# led-wt32-eth01.net
KiCad netlist of a schematic drawn in Altium Designer
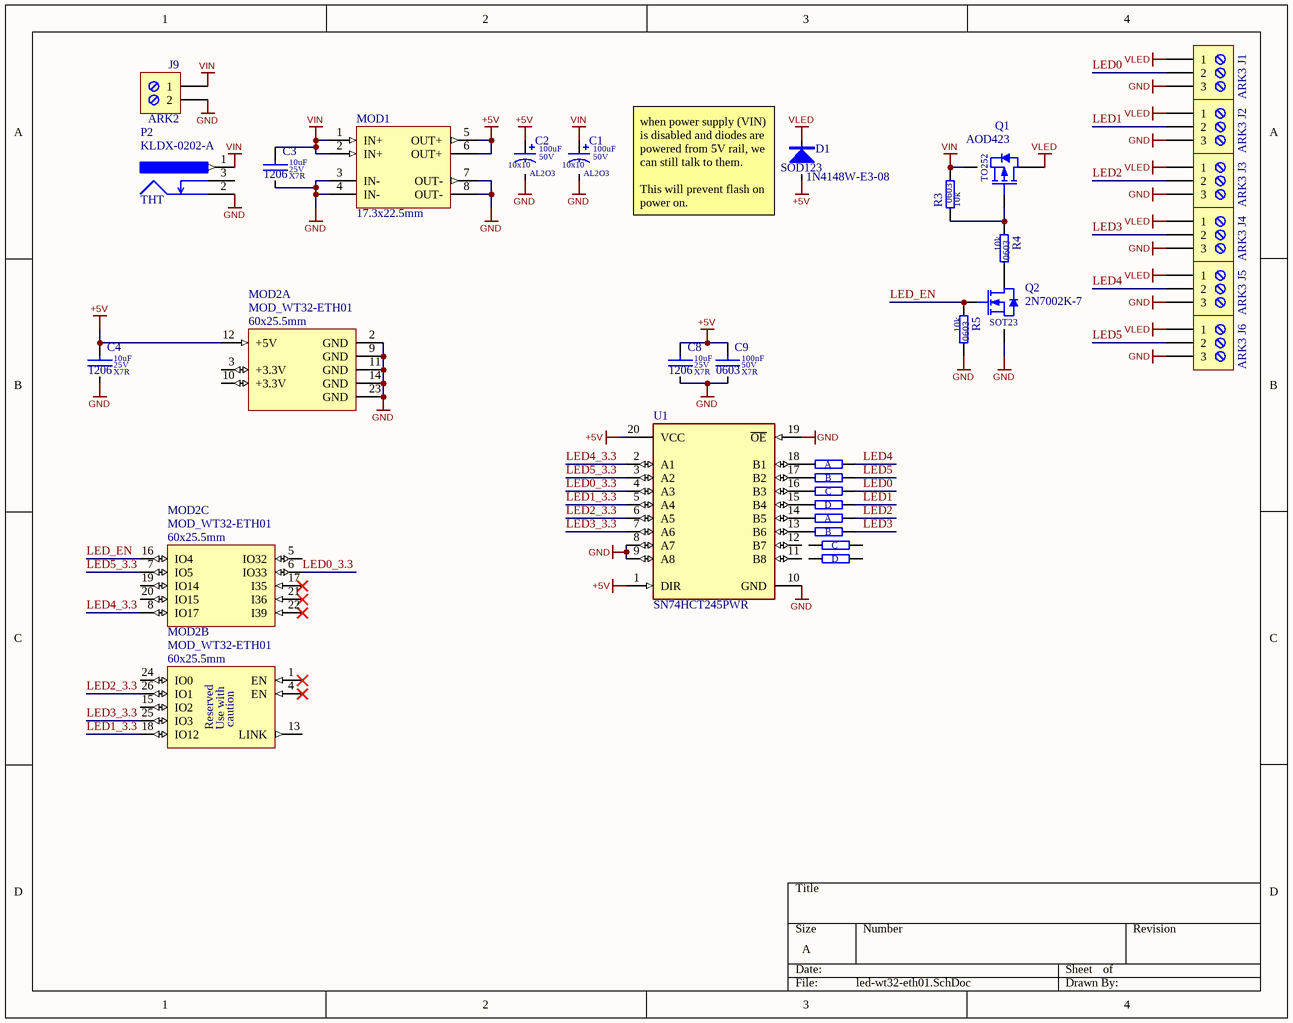
[diagram p0: led-wt32-eth01.SchDoc]

(export (version "E")
  (design (tool "Eeschema 10.0.6"))
  (components
    (comp (ref "C1")
      (value "100uF")
      (footprint "CE_D_10x10_SMD")
      (description "Polarized Capacitor")
      (fields
        (field (name "DIELECTRIC") "AL2O3")
        (field (name "SCH_FOOTPRINT") "10x10")
        (field (name "VOLTAGE") "50V")
        (field (name "PART NUMBER") "CE_100uF_50V_AL2O3_10x10_20")
        (field (name "MANUFACTURER") "Nichicon")
      )
      (libsource (lib "Library") (part "CE"))
    )
    (comp (ref "C2")
      (value "100uF")
      (footprint "CE_D_10x10_SMD")
      (description "Polarized Capacitor")
      (fields
        (field (name "DIELECTRIC") "AL2O3")
        (field (name "SCH_FOOTPRINT") "10x10")
        (field (name "VOLTAGE") "50V")
        (field (name "PART NUMBER") "CE_100uF_50V_AL2O3_10x10_20")
        (field (name "MANUFACTURER") "Nichicon")
      )
      (libsource (lib "Library") (part "CE"))
    )
    (comp (ref "C3")
      (value "10uF")
      (footprint "C_1206_3216")
      (description "Capacitor")
      (fields
        (field (name "DIELECTRIC") "X7R")
        (field (name "VOLTAGE") "25V")
        (field (name "SCH_FOOTPRINT") "1206")
        (field (name "PART NUMBER") "C_10uF_25V_X7R_1206_10")
        (field (name "MANUFACTURER") "Samsung")
      )
      (libsource (lib "Library") (part "C"))
    )
    (comp (ref "C4")
      (value "10uF")
      (footprint "C_1206_3216")
      (description "Capacitor")
      (fields
        (field (name "DIELECTRIC") "X7R")
        (field (name "VOLTAGE") "25V")
        (field (name "SCH_FOOTPRINT") "1206")
        (field (name "PART NUMBER") "C_10uF_25V_X7R_1206_10")
        (field (name "MANUFACTURER") "Samsung")
      )
      (libsource (lib "Library") (part "C"))
    )
    (comp (ref "C8")
      (value "10uF")
      (footprint "C_1206_3216")
      (description "Capacitor")
      (fields
        (field (name "DIELECTRIC") "X7R")
        (field (name "VOLTAGE") "25V")
        (field (name "SCH_FOOTPRINT") "1206")
        (field (name "PART NUMBER") "C_10uF_25V_X7R_1206_10")
        (field (name "MANUFACTURER") "Samsung")
      )
      (libsource (lib "Library") (part "C"))
    )
    (comp (ref "C9")
      (value "100nF")
      (footprint "C_0603_1608")
      (description "Capacitor")
      (fields
        (field (name "DIELECTRIC") "X7R")
        (field (name "VOLTAGE") "50V")
        (field (name "SCH_FOOTPRINT") "0603")
        (field (name "PART NUMBER") "C_100nF_50V_X7R_0603_5")
        (field (name "MANUFACTURER") "Samsung")
      )
      (libsource (lib "Library") (part "C"))
    )
    (comp (ref "D1")
      (value "1N4148W-E3-08")
      (footprint "SOD123")
      (fields
        (field (name "SCH_FOOTPRINT") "SOD123")
        (field (name "PART NUMBER") "D_1N4148W_0A15_75V_SOD123")
        (field (name "VOLTAGE") "75")
        (field (name "MANUFACTURER") "Vishay")
      )
      (libsource (lib "Library") (part "D"))
    )
    (comp (ref "J1")
      (value "ARK3")
      (footprint "J_ARK3")
      (description "ARK Screw terminal, 3-Pin")
      (fields
        (field (name "SCH_FOOTPRINT") "ARK3")
        (field (name "PART NUMBER") "J_TB-5.0-P-3P")
        (field (name "MANUFACTURER") "DEGSON ELECTRONICS")
      )
      (libsource (lib "Library") (part "J_ARK3"))
    )
    (comp (ref "J2")
      (value "ARK3")
      (footprint "J_ARK3")
      (description "ARK Screw terminal, 3-Pin")
      (fields
        (field (name "SCH_FOOTPRINT") "ARK3")
        (field (name "PART NUMBER") "J_TB-5.0-P-3P")
        (field (name "MANUFACTURER") "DEGSON ELECTRONICS")
      )
      (libsource (lib "Library") (part "J_ARK3"))
    )
    (comp (ref "J3")
      (value "ARK3")
      (footprint "J_ARK3")
      (description "ARK Screw terminal, 3-Pin")
      (fields
        (field (name "SCH_FOOTPRINT") "ARK3")
        (field (name "PART NUMBER") "J_TB-5.0-P-3P")
        (field (name "MANUFACTURER") "DEGSON ELECTRONICS")
      )
      (libsource (lib "Library") (part "J_ARK3"))
    )
    (comp (ref "J4")
      (value "ARK3")
      (footprint "J_ARK3")
      (description "ARK Screw terminal, 3-Pin")
      (fields
        (field (name "SCH_FOOTPRINT") "ARK3")
        (field (name "PART NUMBER") "J_TB-5.0-P-3P")
        (field (name "MANUFACTURER") "DEGSON ELECTRONICS")
      )
      (libsource (lib "Library") (part "J_ARK3"))
    )
    (comp (ref "J5")
      (value "ARK3")
      (footprint "J_ARK3")
      (description "ARK Screw terminal, 3-Pin")
      (fields
        (field (name "SCH_FOOTPRINT") "ARK3")
        (field (name "PART NUMBER") "J_TB-5.0-P-3P")
        (field (name "MANUFACTURER") "DEGSON ELECTRONICS")
      )
      (libsource (lib "Library") (part "J_ARK3"))
    )
    (comp (ref "J6")
      (value "ARK3")
      (footprint "J_ARK3")
      (description "ARK Screw terminal, 3-Pin")
      (fields
        (field (name "SCH_FOOTPRINT") "ARK3")
        (field (name "PART NUMBER") "J_TB-5.0-P-3P")
        (field (name "MANUFACTURER") "DEGSON ELECTRONICS")
      )
      (libsource (lib "Library") (part "J_ARK3"))
    )
    (comp (ref "J9")
      (value "ARK2")
      (footprint "J_ARK2")
      (description "ARK Screw terminal, 2-Pin")
      (fields
        (field (name "SCH_FOOTPRINT") "ARK2")
        (field (name "PART NUMBER") "J_TB-5.0-P-2P")
        (field (name "MANUFACTURER") "DEGSON ELECTRONICS")
      )
      (libsource (lib "Library") (part "J_ARK2"))
    )
    (comp (ref "MOD1")
      (value "Low cost, Aliexpress-ready DC-DC buck converter using MP1584")
      (footprint "MOD_BUCK_MP1584")
      (fields (field (name "SCH_FOOTPRINT") "17.3x22.5mm") (field (name "PART NUMBER") "MOD_BUCK_MP1584"))
      (libsource (lib "Library") (part "MOD_BUCK_MP1584"))
    )
    (comp (ref "MOD2")
      (value "MOD_WT32-ETH01")
      (footprint "MOD_WT32-ETH01")
      (fields
        (field (name "SCH_FOOTPRINT") "60x25.5mm")
        (field (name "MANUFACTURER") "WT")
        (field (name "Comment") "ESP32 with 10/100 Mbps Ethernet PHY")
      )
      (libsource (lib "Library") (part "MOD_WT32-ETH01"))
    )
    (comp (ref "P2")
      (value "KLDX-0202-A")
      (footprint "P_KLDX-0202-A")
      (description "Typical 3-pin jack power connector with switch")
      (fields
        (field (name "SCH_FOOTPRINT") "THT")
        (field (name "PART NUMBER") "P_KLDX-0202-A")
        (field (name "MANUFACTURER") "Kycon")
      )
      (libsource (lib "Library") (part "P_DC_JACK"))
    )
    (comp (ref "Q1")
      (value "AOD423")
      (footprint "DPAK_TO252-3_SC63_M")
      (fields
        (field (name "SCH_FOOTPRINT") "TO252")
        (field (name "PART NUMBER") "QP_AOD423")
        (field (name "VOLTAGE") "30V")
        (field (name "MANUFACTURER") "Alpha&Omega Semiconductor")
      )
      (libsource (lib "Library") (part "QP_GDS"))
    )
    (comp (ref "Q2")
      (value "2N7002K-7")
      (footprint "SOT23_TO236_SC59")
      (fields
        (field (name "SCH_FOOTPRINT") "SOT23")
        (field (name "PART NUMBER") "QN_2N7002K-7")
        (field (name "VOLTAGE") "60V")
        (field (name "MANUFACTURER") "Diodes Inc")
      )
      (libsource (lib "Library") (part "QN_GSD"))
    )
    (comp (ref "R3")
      (value "10k")
      (footprint "R_0603_1608")
      (fields
        (field (name "SCH_FOOTPRINT") "0603")
        (field (name "PART NUMBER") "R_10k_0603_1")
        (field (name "VOLTAGE") "75V")
        (field (name "POWER") "100mW")
      )
      (libsource (lib "Library") (part "R"))
    )
    (comp (ref "R4")
      (value "10k")
      (footprint "R_0603_1608")
      (fields
        (field (name "SCH_FOOTPRINT") "0603")
        (field (name "PART NUMBER") "R_10k_0603_1")
        (field (name "VOLTAGE") "75V")
        (field (name "POWER") "100mW")
      )
      (libsource (lib "Library") (part "R"))
    )
    (comp (ref "R5")
      (value "10k")
      (footprint "R_0603_1608")
      (fields
        (field (name "SCH_FOOTPRINT") "0603")
        (field (name "PART NUMBER") "R_10k_0603_1")
        (field (name "VOLTAGE") "75V")
        (field (name "POWER") "100mW")
      )
      (libsource (lib "Library") (part "R"))
    )
    (comp (ref "RN1")
      (value "Resistors Network")
      (footprint "RN4_0804_2010")
      (fields
        (field (name "PART NUMBER") "RN4_120R_0804_5")
        (field (name "VOLTAGE") "50V")
        (field (name "POWER") "63mW")
      )
      (libsource (lib "Library") (part "RN4"))
    )
    (comp (ref "RN2")
      (value "Resistors Network")
      (footprint "RN4_0804_2010")
      (fields
        (field (name "PART NUMBER") "RN4_120R_0804_5")
        (field (name "VOLTAGE") "50V")
        (field (name "POWER") "63mW")
      )
      (libsource (lib "Library") (part "RN4"))
    )
    (comp (ref "U1")
      (value "SN74HCT245PWR")
      (footprint "FP-PW0020A-MFG")
      (description "IC TXRX NON-INVERT 5.5V 20TSSOP")
      (libsource (lib "Altium Content Vault") (part "76fe970679da0e390ff693ee897d809"))
    )
  )
  (nets
    (net (code "1") (name "+5V") (class "Default")
      (node (ref "C2") (pin "1") (pinfunction "1_1") (pintype "passive"))
      (node (ref "C4") (pin "1") (pinfunction "1_1") (pintype "passive"))
      (node (ref "C8") (pin "1") (pinfunction "1_1") (pintype "passive"))
      (node (ref "C9") (pin "1") (pinfunction "1_1") (pintype "passive"))
      (node (ref "D1") (pin "2") (pintype "passive"))
      (node (ref "MOD1") (pin "5") (pinfunction "OUT+_5") (pintype "output"))
      (node (ref "MOD1") (pin "6") (pinfunction "OUT+_6") (pintype "passive"))
      (node (ref "MOD2") (pin "12") (pinfunction "+5V_12") (pintype "input"))
      (node (ref "U1") (pin "1") (pinfunction "DIR_1") (pintype "input"))
      (node (ref "U1") (pin "20") (pinfunction "VCC_20") (pintype "power_in"))
    )
    (net (code "2") (name "/LED0") (class "Default")
      (node (ref "J1") (pin "2") (pinfunction "2_2") (pintype "passive"))
      (node (ref "RN1") (pin "6") (pinfunction "6_6") (pintype "passive"))
    )
    (net (code "3") (name "/LED0_3.3") (class "Default")
      (node (ref "MOD2") (pin "6") (pinfunction "IO33_6") (pintype "bidirectional"))
      (node (ref "U1") (pin "4") (pinfunction "A3_4") (pintype "bidirectional"))
    )
    (net (code "4") (name "/LED1") (class "Default")
      (node (ref "J2") (pin "2") (pinfunction "2_2") (pintype "passive"))
      (node (ref "RN1") (pin "5") (pinfunction "5_5") (pintype "passive"))
    )
    (net (code "5") (name "/LED1_3.3") (class "Default")
      (node (ref "MOD2") (pin "18") (pinfunction "IO12_18") (pintype "bidirectional"))
      (node (ref "U1") (pin "5") (pinfunction "A4_5") (pintype "bidirectional"))
    )
    (net (code "6") (name "/LED2") (class "Default")
      (node (ref "J3") (pin "2") (pinfunction "2_2") (pintype "passive"))
      (node (ref "RN2") (pin "8") (pinfunction "8_8") (pintype "passive"))
    )
    (net (code "7") (name "/LED2_3.3") (class "Default")
      (node (ref "MOD2") (pin "26") (pinfunction "IO1_26") (pintype "bidirectional"))
      (node (ref "U1") (pin "6") (pinfunction "A5_6") (pintype "bidirectional"))
    )
    (net (code "8") (name "/LED3") (class "Default")
      (node (ref "J4") (pin "2") (pinfunction "2_2") (pintype "passive"))
      (node (ref "RN2") (pin "7") (pinfunction "7_7") (pintype "passive"))
    )
    (net (code "9") (name "/LED3_3.3") (class "Default")
      (node (ref "MOD2") (pin "25") (pinfunction "IO3_25") (pintype "bidirectional"))
      (node (ref "U1") (pin "7") (pinfunction "A6_7") (pintype "bidirectional"))
    )
    (net (code "10") (name "/LED4") (class "Default")
      (node (ref "J5") (pin "2") (pinfunction "2_2") (pintype "passive"))
      (node (ref "RN1") (pin "8") (pinfunction "8_8") (pintype "passive"))
    )
    (net (code "11") (name "/LED4_3.3") (class "Default")
      (node (ref "MOD2") (pin "8") (pinfunction "IO17_8") (pintype "bidirectional"))
      (node (ref "U1") (pin "2") (pinfunction "A1_2") (pintype "bidirectional"))
    )
    (net (code "12") (name "/LED5") (class "Default")
      (node (ref "J6") (pin "2") (pinfunction "2_2") (pintype "passive"))
      (node (ref "RN1") (pin "7") (pinfunction "7_7") (pintype "passive"))
    )
    (net (code "13") (name "/LED5_3.3") (class "Default")
      (node (ref "MOD2") (pin "7") (pinfunction "IO5_7") (pintype "bidirectional"))
      (node (ref "U1") (pin "3") (pinfunction "A2_3") (pintype "bidirectional"))
    )
    (net (code "14") (name "/LED_EN") (class "Default")
      (node (ref "MOD2") (pin "16") (pinfunction "IO4_16") (pintype "bidirectional"))
      (node (ref "Q2") (pin "1") (pinfunction "G_1") (pintype "passive"))
      (node (ref "R5") (pin "1") (pinfunction "1_1") (pintype "passive"))
    )
    (net (code "15") (name "GND") (class "Default")
      (node (ref "C1") (pin "2") (pinfunction "2_2") (pintype "passive"))
      (node (ref "C2") (pin "2") (pinfunction "2_2") (pintype "passive"))
      (node (ref "C3") (pin "2") (pinfunction "2_2") (pintype "passive"))
      (node (ref "C4") (pin "2") (pinfunction "2_2") (pintype "passive"))
      (node (ref "C8") (pin "2") (pinfunction "2_2") (pintype "passive"))
      (node (ref "C9") (pin "2") (pinfunction "2_2") (pintype "passive"))
      (node (ref "J1") (pin "3") (pinfunction "3_3") (pintype "passive"))
      (node (ref "J2") (pin "3") (pinfunction "3_3") (pintype "passive"))
      (node (ref "J3") (pin "3") (pinfunction "3_3") (pintype "passive"))
      (node (ref "J4") (pin "3") (pinfunction "3_3") (pintype "passive"))
      (node (ref "J5") (pin "3") (pinfunction "3_3") (pintype "passive"))
      (node (ref "J6") (pin "3") (pinfunction "3_3") (pintype "passive"))
      (node (ref "J9") (pin "2") (pinfunction "2_2") (pintype "passive"))
      (node (ref "MOD1") (pin "3") (pinfunction "IN-_3") (pintype "power_in"))
      (node (ref "MOD1") (pin "4") (pinfunction "IN-_4") (pintype "power_in"))
      (node (ref "MOD1") (pin "7") (pinfunction "OUT-_7") (pintype "output"))
      (node (ref "MOD1") (pin "8") (pinfunction "OUT-_8") (pintype "passive"))
      (node (ref "MOD2") (pin "11") (pinfunction "GND_11") (pintype "power_in"))
      (node (ref "MOD2") (pin "14") (pinfunction "GND_14") (pintype "power_in"))
      (node (ref "MOD2") (pin "2") (pinfunction "GND_2") (pintype "power_in"))
      (node (ref "MOD2") (pin "23") (pinfunction "GND_23") (pintype "power_in"))
      (node (ref "MOD2") (pin "9") (pinfunction "GND_9") (pintype "power_in"))
      (node (ref "P2") (pin "2") (pinfunction "2_2") (pintype "passive"))
      (node (ref "Q2") (pin "2") (pinfunction "S_2") (pintype "passive"))
      (node (ref "R5") (pin "2") (pinfunction "2_2") (pintype "passive"))
      (node (ref "U1") (pin "10") (pinfunction "GND_10") (pintype "power_in"))
      (node (ref "U1") (pin "19") (pinfunction "~{OE}_19") (pintype "input"))
      (node (ref "U1") (pin "8") (pinfunction "A7_8") (pintype "bidirectional"))
      (node (ref "U1") (pin "9") (pinfunction "A8_9") (pintype "bidirectional"))
    )
    (net (code "16") (name "Net-(Q1-G)") (class "Default")
      (node (ref "Q1") (pin "1") (pinfunction "G_1") (pintype "passive"))
      (node (ref "R3") (pin "1") (pinfunction "1_1") (pintype "passive"))
      (node (ref "R4") (pin "1") (pinfunction "1_1") (pintype "passive"))
    )
    (net (code "17") (name "Net-(Q2-D)") (class "Default")
      (node (ref "Q2") (pin "3") (pinfunction "D_3") (pintype "passive"))
      (node (ref "R4") (pin "2") (pinfunction "2_2") (pintype "passive"))
    )
    (net (code "18") (name "Net-(U1-B1)") (class "Default")
      (node (ref "RN1") (pin "1") (pinfunction "1_1") (pintype "passive"))
      (node (ref "U1") (pin "18") (pinfunction "B1_18") (pintype "bidirectional"))
    )
    (net (code "19") (name "Net-(U1-B2)") (class "Default")
      (node (ref "RN1") (pin "2") (pinfunction "2_2") (pintype "passive"))
      (node (ref "U1") (pin "17") (pinfunction "B2_17") (pintype "bidirectional"))
    )
    (net (code "20") (name "Net-(U1-B3)") (class "Default")
      (node (ref "RN1") (pin "3") (pinfunction "3_3") (pintype "passive"))
      (node (ref "U1") (pin "16") (pinfunction "B3_16") (pintype "bidirectional"))
    )
    (net (code "21") (name "Net-(U1-B4)") (class "Default")
      (node (ref "RN1") (pin "4") (pinfunction "4_4") (pintype "passive"))
      (node (ref "U1") (pin "15") (pinfunction "B4_15") (pintype "bidirectional"))
    )
    (net (code "22") (name "Net-(U1-B5)") (class "Default")
      (node (ref "RN2") (pin "1") (pinfunction "1_1") (pintype "passive"))
      (node (ref "U1") (pin "14") (pinfunction "B5_14") (pintype "bidirectional"))
    )
    (net (code "23") (name "Net-(U1-B6)") (class "Default")
      (node (ref "RN2") (pin "2") (pinfunction "2_2") (pintype "passive"))
      (node (ref "U1") (pin "13") (pinfunction "B6_13") (pintype "bidirectional"))
    )
    (net (code "24") (name "VIN") (class "Default")
      (node (ref "C1") (pin "1") (pinfunction "1_1") (pintype "passive"))
      (node (ref "C3") (pin "1") (pinfunction "1_1") (pintype "passive"))
      (node (ref "J9") (pin "1") (pinfunction "1_1") (pintype "passive"))
      (node (ref "MOD1") (pin "1") (pinfunction "IN+_1") (pintype "input"))
      (node (ref "MOD1") (pin "2") (pinfunction "IN+_2") (pintype "input"))
      (node (ref "P2") (pin "1") (pinfunction "1_1") (pintype "output"))
      (node (ref "Q1") (pin "3") (pinfunction "S_3") (pintype "passive"))
      (node (ref "R3") (pin "2") (pinfunction "2_2") (pintype "passive"))
    )
    (net (code "25") (name "VLED") (class "Default")
      (node (ref "D1") (pin "1") (pintype "passive"))
      (node (ref "J1") (pin "1") (pinfunction "1_1") (pintype "passive"))
      (node (ref "J2") (pin "1") (pinfunction "1_1") (pintype "passive"))
      (node (ref "J3") (pin "1") (pinfunction "1_1") (pintype "passive"))
      (node (ref "J4") (pin "1") (pinfunction "1_1") (pintype "passive"))
      (node (ref "J5") (pin "1") (pinfunction "1_1") (pintype "passive"))
      (node (ref "J6") (pin "1") (pinfunction "1_1") (pintype "passive"))
      (node (ref "Q1") (pin "2") (pinfunction "D_2") (pintype "passive"))
    )
    (net (code "26") (name "unconnected-(MOD2A-+3.3V-Pad3)") (class "Default")
      (node (ref "MOD2") (pin "3") (pinfunction "+3.3V_3") (pintype "bidirectional"))
    )
    (net (code "27") (name "unconnected-(MOD2A-+3.3V-Pad10)") (class "Default")
      (node (ref "MOD2") (pin "10") (pinfunction "+3.3V_10") (pintype "bidirectional"))
    )
    (net (code "28") (name "unconnected-(MOD2B-EN-Pad1)") (class "Default")
      (node (ref "MOD2") (pin "1") (pinfunction "EN_1") (pintype "input+no_connect"))
    )
    (net (code "29") (name "unconnected-(MOD2B-EN-Pad4)") (class "Default")
      (node (ref "MOD2") (pin "4") (pinfunction "EN_4") (pintype "input+no_connect"))
    )
    (net (code "30") (name "unconnected-(MOD2B-IO0-Pad24)") (class "Default")
      (node (ref "MOD2") (pin "24") (pinfunction "IO0_24") (pintype "bidirectional"))
    )
    (net (code "31") (name "unconnected-(MOD2B-IO2-Pad15)") (class "Default")
      (node (ref "MOD2") (pin "15") (pinfunction "IO2_15") (pintype "bidirectional"))
    )
    (net (code "32") (name "unconnected-(MOD2B-LINK-Pad13)") (class "Default")
      (node (ref "MOD2") (pin "13") (pinfunction "LINK_13") (pintype "output"))
    )
    (net (code "33") (name "unconnected-(MOD2C-I35-Pad17)") (class "Default")
      (node (ref "MOD2") (pin "17") (pinfunction "I35_17") (pintype "input+no_connect"))
    )
    (net (code "34") (name "unconnected-(MOD2C-I36-Pad21)") (class "Default")
      (node (ref "MOD2") (pin "21") (pinfunction "I36_21") (pintype "input+no_connect"))
    )
    (net (code "35") (name "unconnected-(MOD2C-I39-Pad22)") (class "Default")
      (node (ref "MOD2") (pin "22") (pinfunction "I39_22") (pintype "input+no_connect"))
    )
    (net (code "36") (name "unconnected-(MOD2C-IO14-Pad19)") (class "Default")
      (node (ref "MOD2") (pin "19") (pinfunction "IO14_19") (pintype "bidirectional"))
    )
    (net (code "37") (name "unconnected-(MOD2C-IO15-Pad20)") (class "Default")
      (node (ref "MOD2") (pin "20") (pinfunction "IO15_20") (pintype "bidirectional"))
    )
    (net (code "38") (name "unconnected-(MOD2C-IO32-Pad5)") (class "Default")
      (node (ref "MOD2") (pin "5") (pinfunction "IO32_5") (pintype "bidirectional"))
    )
    (net (code "39") (name "unconnected-(P2-Pad3)") (class "Default")
      (node (ref "P2") (pin "3") (pinfunction "3_3") (pintype "passive"))
    )
    (net (code "40") (name "unconnected-(RN2-Pad3)") (class "Default")
      (node (ref "RN2") (pin "3") (pinfunction "3_3") (pintype "passive"))
    )
    (net (code "41") (name "unconnected-(RN2-Pad4)") (class "Default")
      (node (ref "RN2") (pin "4") (pinfunction "4_4") (pintype "passive"))
    )
    (net (code "42") (name "unconnected-(RN2-Pad5)") (class "Default")
      (node (ref "RN2") (pin "5") (pinfunction "5_5") (pintype "passive"))
    )
    (net (code "43") (name "unconnected-(RN2-Pad6)") (class "Default")
      (node (ref "RN2") (pin "6") (pinfunction "6_6") (pintype "passive"))
    )
    (net (code "44") (name "unconnected-(U1-B7-Pad12)") (class "Default")
      (node (ref "U1") (pin "12") (pinfunction "B7_12") (pintype "bidirectional"))
    )
    (net (code "45") (name "unconnected-(U1-B8-Pad11)") (class "Default")
      (node (ref "U1") (pin "11") (pinfunction "B8_11") (pintype "bidirectional"))
    )
  )
)
